# FYP_Programmer.net
KiCad netlist of a schematic drawn in EasyEDA
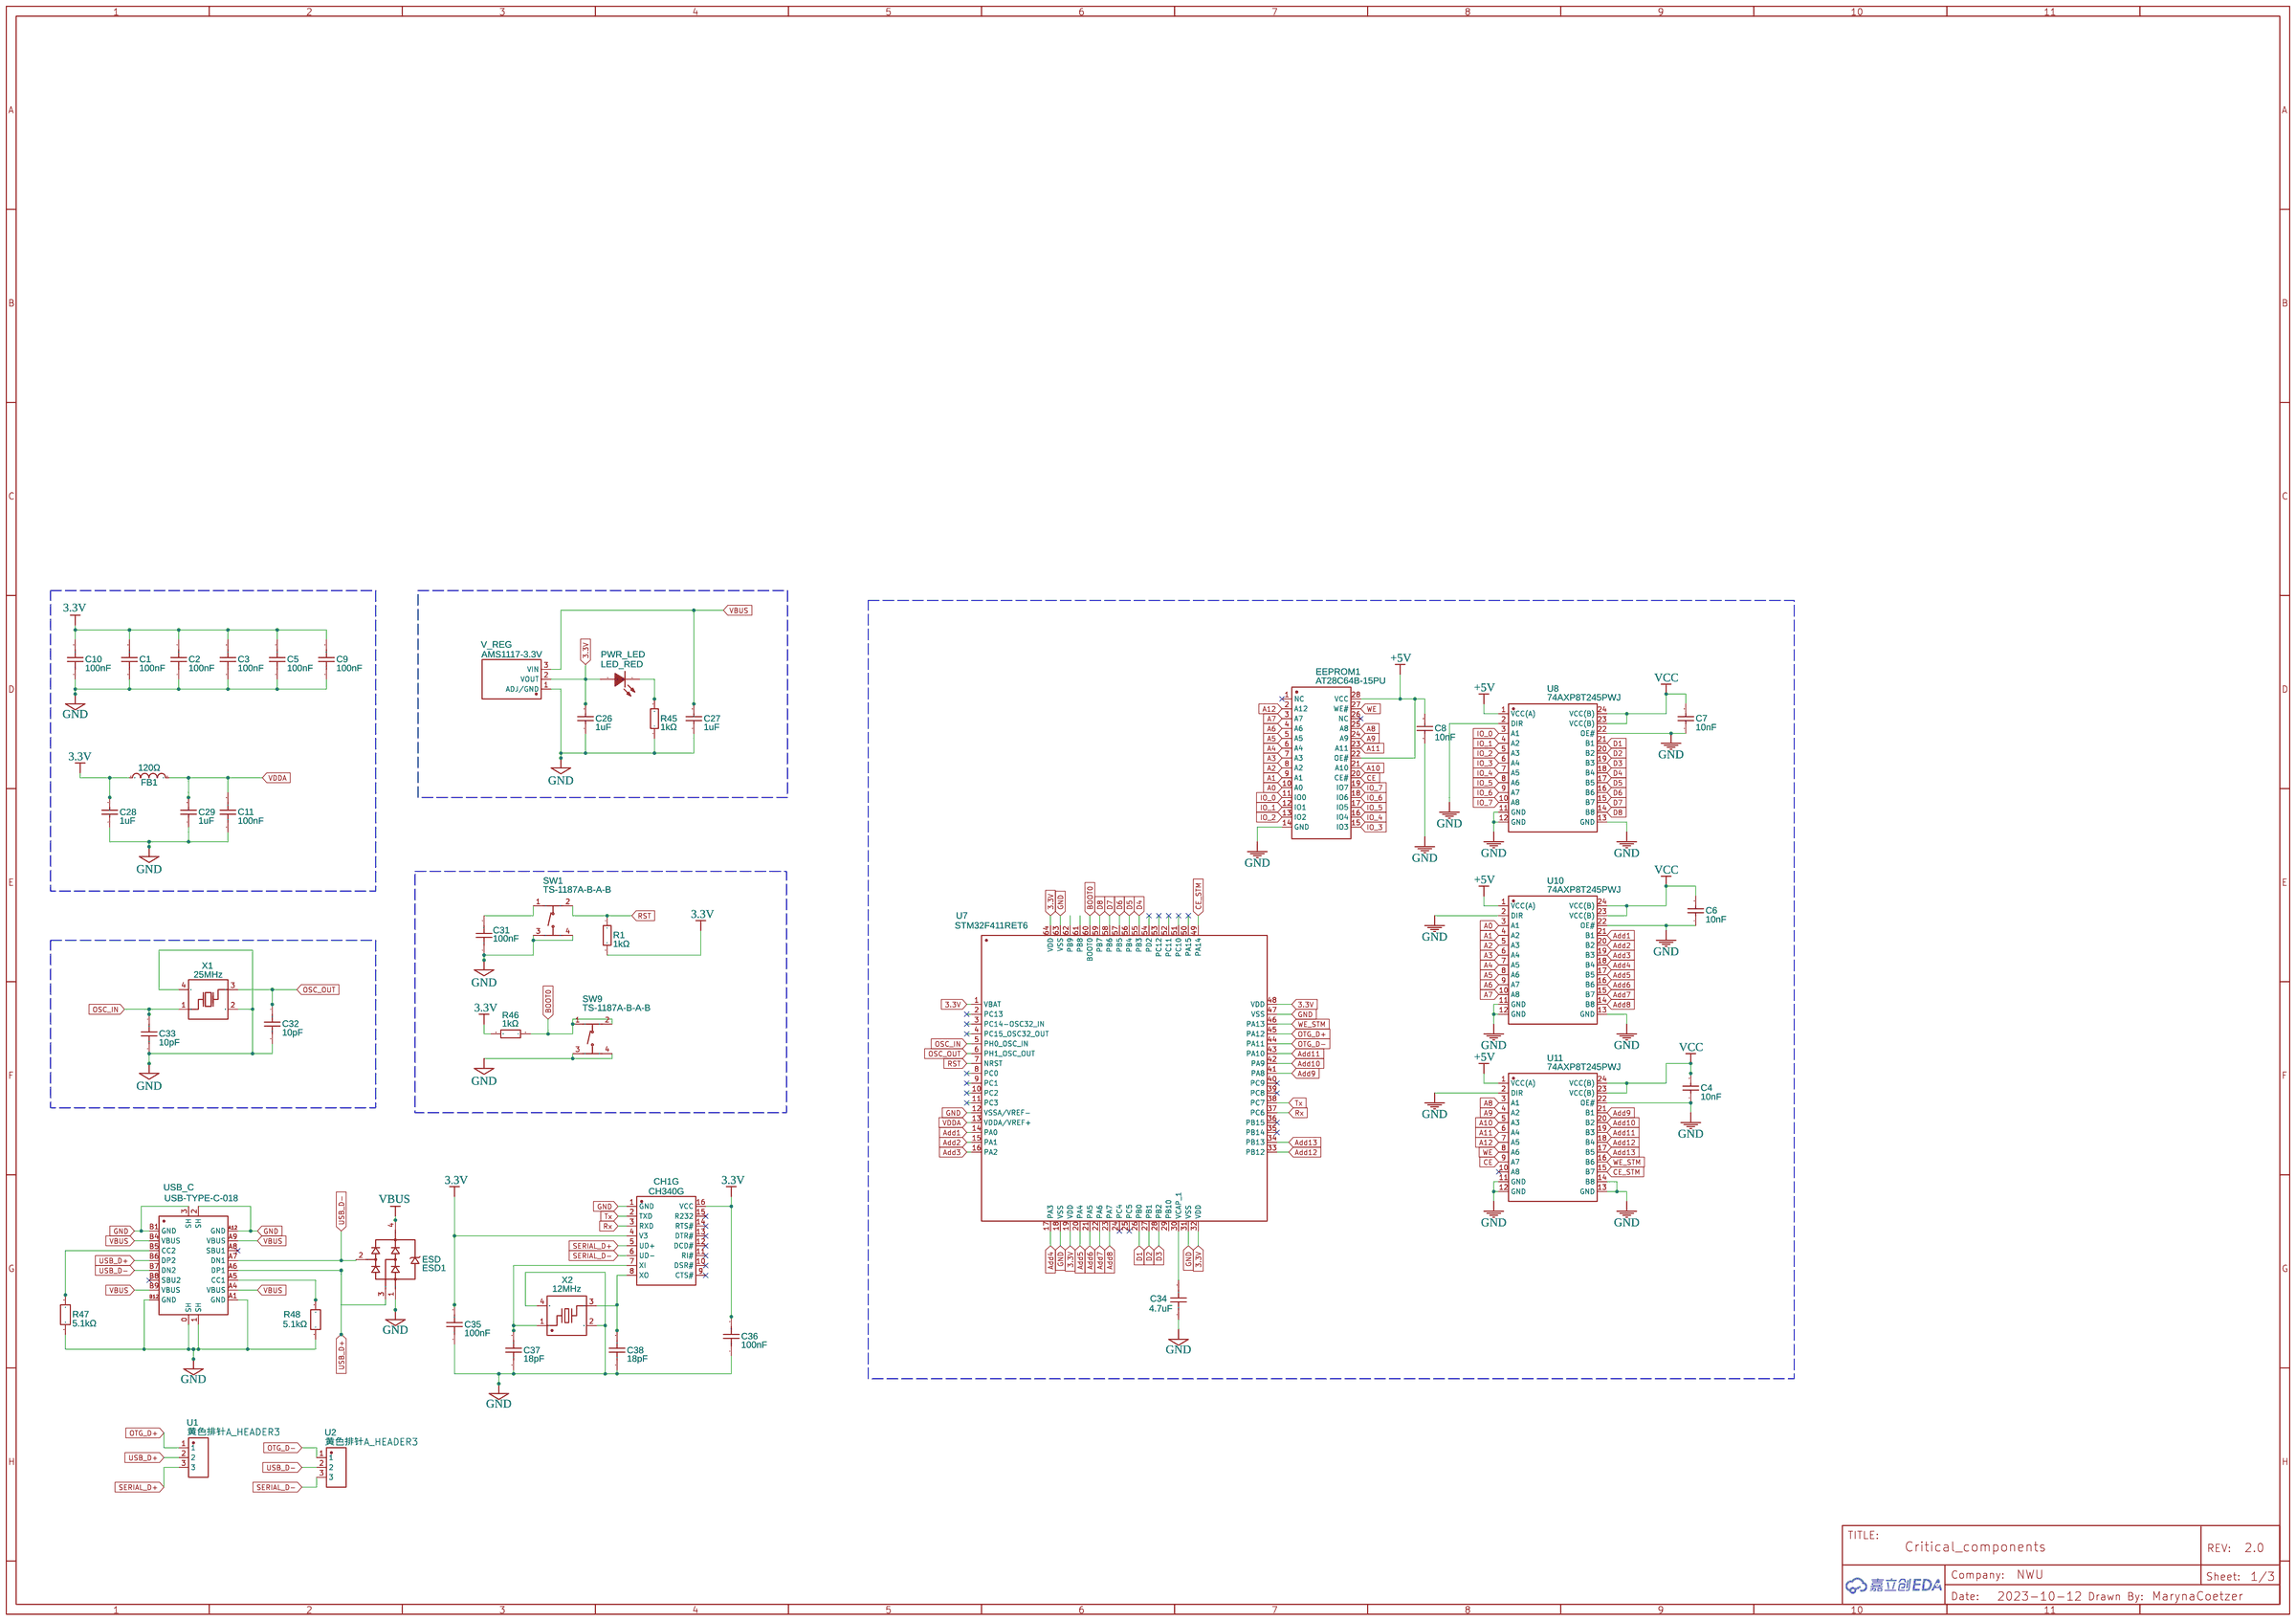
[diagram p0: schematic sheet]

(export (version "E")
  (design (tool "Eeschema 10.0.6"))
  (components
    (comp (ref "C1")
      (value "100nF")
      (fields
        (field (name "Manufacturer Part") "CC0603KRX7R9BB104")
        (field (name "Manufacturer") "YAGEO(国巨)")
      )
      (libsource (lib "") (part "CC0603KRX7R9BB104"))
    )
    (comp (ref "C2")
      (value "100nF")
      (fields
        (field (name "Manufacturer Part") "CC0603KRX7R9BB104")
        (field (name "Manufacturer") "YAGEO(国巨)")
      )
      (libsource (lib "") (part "CC0603KRX7R9BB104"))
    )
    (comp (ref "C3")
      (value "100nF")
      (fields
        (field (name "Manufacturer Part") "CC0603KRX7R9BB104")
        (field (name "Manufacturer") "YAGEO(国巨)")
      )
      (libsource (lib "") (part "CC0603KRX7R9BB104"))
    )
    (comp (ref "C4")
      (value "10nF")
      (fields (field (name "Manufacturer Part") "0603B103K500NT") (field (name "Manufacturer") "FH(风华)"))
      (libsource (lib "") (part "0603B103K500NT"))
    )
    (comp (ref "C5")
      (value "100nF")
      (fields
        (field (name "Manufacturer Part") "CC0603KRX7R9BB104")
        (field (name "Manufacturer") "YAGEO(国巨)")
      )
      (libsource (lib "") (part "CC0603KRX7R9BB104"))
    )
    (comp (ref "C6")
      (value "10nF")
      (fields (field (name "Manufacturer Part") "0603B103K500NT") (field (name "Manufacturer") "FH(风华)"))
      (libsource (lib "") (part "0603B103K500NT"))
    )
    (comp (ref "C7")
      (value "10nF")
      (fields (field (name "Manufacturer Part") "0603B103K500NT") (field (name "Manufacturer") "FH(风华)"))
      (libsource (lib "") (part "0603B103K500NT"))
    )
    (comp (ref "C8")
      (value "10nF")
      (fields (field (name "Manufacturer Part") "0603B103K500NT") (field (name "Manufacturer") "FH(风华)"))
      (libsource (lib "") (part "0603B103K500NT"))
    )
    (comp (ref "C9")
      (value "100nF")
      (fields
        (field (name "Manufacturer Part") "CC0603KRX7R9BB104")
        (field (name "Manufacturer") "YAGEO(国巨)")
      )
      (libsource (lib "") (part "CC0603KRX7R9BB104"))
    )
    (comp (ref "C10")
      (value "100nF")
      (fields
        (field (name "Manufacturer Part") "CC0603KRX7R9BB104")
        (field (name "Manufacturer") "YAGEO(国巨)")
      )
      (libsource (lib "") (part "CC0603KRX7R9BB104"))
    )
    (comp (ref "C11")
      (value "100nF")
      (fields
        (field (name "Manufacturer Part") "CC0603KRX7R9BB104")
        (field (name "Manufacturer") "YAGEO(国巨)")
      )
      (libsource (lib "") (part "CC0603KRX7R9BB104"))
    )
    (comp (ref "C26")
      (value "1uF")
      (fields (field (name "Manufacturer") "SAMSUNG(三星)"))
      (libsource (lib "") (part "CL10A105KB8NNNC"))
    )
    (comp (ref "C27")
      (value "1uF")
      (fields (field (name "Manufacturer") "SAMSUNG(三星)"))
      (libsource (lib "") (part "CL10A105KB8NNNC"))
    )
    (comp (ref "C28")
      (value "1uF")
      (fields (field (name "Manufacturer") "SAMSUNG(三星)"))
      (libsource (lib "") (part "CL10A105KB8NNNC"))
    )
    (comp (ref "C29")
      (value "1uF")
      (fields (field (name "Manufacturer") "SAMSUNG(三星)"))
      (libsource (lib "") (part "CL10A105KB8NNNC"))
    )
    (comp (ref "C31")
      (value "100nF")
      (fields (field (name "Manufacturer Part") "C1608X7R104KFTS") (field (name "Manufacturer") "DARFON(达方)"))
      (libsource (lib "") (part "C1608X7R104KFTS"))
    )
    (comp (ref "C32")
      (value "10pF")
      (fields (field (name "Manufacturer") "muRata(村田)"))
      (libsource (lib "") (part "GJM1555C1H100JB01D"))
    )
    (comp (ref "C33")
      (value "10pF")
      (fields (field (name "Manufacturer") "muRata(村田)"))
      (libsource (lib "") (part "GJM1555C1H100JB01D"))
    )
    (comp (ref "C34")
      (value "4.7uF")
      (fields (field (name "Manufacturer") "muRata(村田)"))
      (libsource (lib "") (part "GRM188R61C475KE11D"))
    )
    (comp (ref "C35")
      (value "100nF")
      (fields (field (name "Manufacturer") "Kyocera AVX"))
      (libsource (lib "") (part "06033C104K4T2A"))
    )
    (comp (ref "C36")
      (value "100nF")
      (fields (field (name "Manufacturer") "Kyocera AVX"))
      (libsource (lib "") (part "06033C104K4T2A"))
    )
    (comp (ref "C37")
      (value "18pF")
      (fields
        (field (name "Manufacturer Part") "AC0603JRNPO0BN220")
        (field (name "Manufacturer") "YAGEO(国巨)")
      )
      (libsource (lib "") (part "AC0603JRNPO0BN220"))
    )
    (comp (ref "C38")
      (value "18pF")
      (fields
        (field (name "Manufacturer Part") "AC0603JRNPO0BN220")
        (field (name "Manufacturer") "YAGEO(国巨)")
      )
      (libsource (lib "") (part "AC0603JRNPO0BN220"))
    )
    (comp (ref "CH1G")
      (value "CH340G")
      (fields (field (name "Manufacturer") "WCH(南京沁恒)"))
      (libsource (lib "") (part "CH340G"))
    )
    (comp (ref "EEPROM1")
      (value "AT28C64B-15PU")
      (fields (field (name "Manufacturer") "MICROCHIP(美国微芯)"))
      (libsource (lib "") (part "AT28C64B-15PU"))
    )
    (comp (ref "ESD")
      (value "ESD1")
      (fields
        (field (name "Manufacturer Part") "TPPRTR5V0U2X")
        (field (name "Manufacturer") "TECH PUBLIC(台舟)")
      )
      (libsource (lib "") (part "TPPRTR5V0U2X"))
    )
    (comp (ref "FB1")
      (value "120Ω")
      (fields (field (name "Manufacturer Part") "GZ1608D121TF") (field (name "Manufacturer") "Sunlord(顺络)"))
      (libsource (lib "") (part "GZ1608D121TF-C12391"))
    )
    (comp (ref "PWR_LED")
      (value "LED_RED")
      (fields (field (name "Manufacturer") "国星光电"))
      (libsource (lib "") (part "FC-2012HRK-620D"))
    )
    (comp (ref "R1")
      (value "1kΩ")
      (fields (field (name "Manufacturer") "UNI-ROYAL(厚声)"))
      (libsource (lib "") (part "0603WAF1001T5E_1"))
    )
    (comp (ref "R45")
      (value "1kΩ")
      (fields (field (name "Manufacturer Part") "RMS06FT1001") (field (name "Manufacturer") "大毅科技"))
      (libsource (lib "") (part "RMS06FT1001"))
    )
    (comp (ref "R46")
      (value "1kΩ")
      (fields (field (name "Manufacturer") "UNI-ROYAL(厚声)"))
      (libsource (lib "") (part "0603WAF1001T5E"))
    )
    (comp (ref "R47")
      (value "5.1kΩ")
      (fields
        (field (name "Manufacturer Part") "CQ03WAJ0512T5E")
        (field (name "Manufacturer") "UNI-ROYAL(厚声)")
      )
      (libsource (lib "") (part "CQ03WAJ0512T5E"))
    )
    (comp (ref "R48")
      (value "5.1kΩ")
      (fields
        (field (name "Manufacturer Part") "CQ03WAJ0512T5E")
        (field (name "Manufacturer") "UNI-ROYAL(厚声)")
      )
      (libsource (lib "") (part "CQ03WAJ0512T5E"))
    )
    (comp (ref "SW1")
      (value "TS-1187A-B-A-B")
      (fields (field (name "Manufacturer") "XKB Connection(中国星坤)"))
      (libsource (lib "") (part "TS-1187A-B-A-B"))
    )
    (comp (ref "SW9")
      (value "TS-1187A-B-A-B")
      (fields (field (name "Manufacturer") "XKB Connection(中国星坤)"))
      (libsource (lib "") (part "TS-1187A-B-A-B"))
    )
    (comp (ref "U1") (value "黄色排针A_HEADER3") (libsource (lib "") (part "黄色排针A_HEADER3")))
    (comp (ref "U2") (value "黄色排针A_HEADER3") (libsource (lib "") (part "黄色排针A_HEADER3")))
    (comp (ref "U7")
      (value "STM32F411RET6")
      (fields (field (name "Manufacturer") "ST(意法半导体)"))
      (libsource (lib "") (part "STM32F411RET6"))
    )
    (comp (ref "U8")
      (value "74AXP8T245PWJ")
      (fields (field (name "Manufacturer") "Nexperia(安世)"))
      (libsource (lib "") (part "74AXP8T245PWJ"))
    )
    (comp (ref "U10")
      (value "74AXP8T245PWJ")
      (fields (field (name "Manufacturer") "Nexperia(安世)"))
      (libsource (lib "") (part "74AXP8T245PWJ"))
    )
    (comp (ref "U11")
      (value "74AXP8T245PWJ")
      (fields (field (name "Manufacturer") "Nexperia(安世)"))
      (libsource (lib "") (part "74AXP8T245PWJ"))
    )
    (comp (ref "USB_C")
      (value "USB-TYPE-C-018")
      (fields (field (name "Manufacturer") "DEALON(德艺隆)"))
      (libsource (lib "") (part "USB-TYPE-C-018"))
    )
    (comp (ref "V_REG")
      (value "AMS1117-3.3V")
      (fields (field (name "Manufacturer") "MSKSEMI(美森科)"))
      (libsource (lib "") (part "AMS1117-3.3V_C5120796"))
    )
    (comp (ref "X1")
      (value "25MHz")
      (fields (field (name "Manufacturer Part") "X322525MMB4SI") (field (name "Manufacturer") "YXC(扬兴晶振)"))
      (libsource (lib "") (part "X322525MMB4SI"))
    )
    (comp (ref "X2")
      (value "12MHz")
      (fields (field (name "Manufacturer") "HD(浩都频率)"))
      (libsource (lib "") (part "7B012000Q01"))
    )
  )
  (nets
    (net (code "1") (name "+5V") (class "Default")
      (node (ref "C8") (pin "2") (pinfunction "2_2") (pintype "input"))
      (node (ref "EEPROM1") (pin "22") (pinfunction "OE#_22") (pintype "unspecified"))
      (node (ref "EEPROM1") (pin "28") (pinfunction "VCC_28") (pintype "unspecified"))
      (node (ref "U10") (pin "1") (pinfunction "VCC(A)_1") (pintype "unspecified"))
      (node (ref "U11") (pin "1") (pinfunction "VCC(A)_1") (pintype "unspecified"))
      (node (ref "U8") (pin "1") (pinfunction "VCC(A)_1") (pintype "unspecified"))
    )
    (net (code "2") (name "3.3V") (class "Default")
      (node (ref "C1") (pin "2") (pinfunction "2_2") (pintype "unspecified"))
      (node (ref "C10") (pin "2") (pinfunction "2_2") (pintype "unspecified"))
      (node (ref "C2") (pin "2") (pinfunction "2_2") (pintype "unspecified"))
      (node (ref "C26") (pin "2") (pinfunction "2_2") (pintype "input"))
      (node (ref "C28") (pin "2") (pinfunction "2_2") (pintype "input"))
      (node (ref "C3") (pin "2") (pinfunction "2_2") (pintype "unspecified"))
      (node (ref "C35") (pin "2") (pinfunction "2_2") (pintype "unspecified"))
      (node (ref "C36") (pin "2") (pinfunction "2_2") (pintype "unspecified"))
      (node (ref "C5") (pin "2") (pinfunction "2_2") (pintype "unspecified"))
      (node (ref "C9") (pin "2") (pinfunction "2_2") (pintype "unspecified"))
      (node (ref "CH1G") (pin "16") (pinfunction "VCC_16") (pintype "unspecified"))
      (node (ref "CH1G") (pin "4") (pinfunction "V3_4") (pintype "unspecified"))
      (node (ref "FB1") (pin "1") (pinfunction "1_1") (pintype "unspecified"))
      (node (ref "PWR_LED") (pin "2") (pinfunction "+_2") (pintype "unspecified"))
      (node (ref "R1") (pin "2") (pinfunction "2_2") (pintype "input"))
      (node (ref "R46") (pin "2") (pinfunction "2_2") (pintype "input"))
      (node (ref "U7") (pin "1") (pinfunction "VBAT_1") (pintype "unspecified"))
      (node (ref "U7") (pin "19") (pinfunction "VDD_19") (pintype "unspecified"))
      (node (ref "U7") (pin "32") (pinfunction "VDD_32") (pintype "unspecified"))
      (node (ref "U7") (pin "48") (pinfunction "VDD_48") (pintype "unspecified"))
      (node (ref "U7") (pin "64") (pinfunction "VDD_64") (pintype "unspecified"))
      (node (ref "V_REG") (pin "2") (pinfunction "VOUT_2") (pintype "unspecified"))
    )
    (net (code "3") (name "A0") (class "Default")
      (node (ref "EEPROM1") (pin "10") (pinfunction "A0_10") (pintype "unspecified"))
      (node (ref "U10") (pin "3") (pinfunction "A1_3") (pintype "unspecified"))
    )
    (net (code "4") (name "A1") (class "Default")
      (node (ref "EEPROM1") (pin "9") (pinfunction "A1_9") (pintype "unspecified"))
      (node (ref "U10") (pin "4") (pinfunction "A2_4") (pintype "unspecified"))
    )
    (net (code "5") (name "A2") (class "Default")
      (node (ref "EEPROM1") (pin "8") (pinfunction "A2_8") (pintype "unspecified"))
      (node (ref "U10") (pin "5") (pinfunction "A3_5") (pintype "unspecified"))
    )
    (net (code "6") (name "A3") (class "Default")
      (node (ref "EEPROM1") (pin "7") (pinfunction "A3_7") (pintype "unspecified"))
      (node (ref "U10") (pin "6") (pinfunction "A4_6") (pintype "unspecified"))
    )
    (net (code "7") (name "A4") (class "Default")
      (node (ref "EEPROM1") (pin "6") (pinfunction "A4_6") (pintype "unspecified"))
      (node (ref "U10") (pin "7") (pinfunction "A5_7") (pintype "unspecified"))
    )
    (net (code "8") (name "A5") (class "Default")
      (node (ref "EEPROM1") (pin "5") (pinfunction "A5_5") (pintype "unspecified"))
      (node (ref "U10") (pin "8") (pinfunction "A6_8") (pintype "unspecified"))
    )
    (net (code "9") (name "A6") (class "Default")
      (node (ref "EEPROM1") (pin "4") (pinfunction "A6_4") (pintype "unspecified"))
      (node (ref "U10") (pin "9") (pinfunction "A7_9") (pintype "unspecified"))
    )
    (net (code "10") (name "A7") (class "Default")
      (node (ref "EEPROM1") (pin "3") (pinfunction "A7_3") (pintype "unspecified"))
      (node (ref "U10") (pin "10") (pinfunction "A8_10") (pintype "unspecified"))
    )
    (net (code "11") (name "A8") (class "Default")
      (node (ref "EEPROM1") (pin "25") (pinfunction "A8_25") (pintype "unspecified"))
      (node (ref "U11") (pin "3") (pinfunction "A1_3") (pintype "unspecified"))
    )
    (net (code "12") (name "A9") (class "Default")
      (node (ref "EEPROM1") (pin "24") (pinfunction "A9_24") (pintype "unspecified"))
      (node (ref "U11") (pin "4") (pinfunction "A2_4") (pintype "unspecified"))
    )
    (net (code "13") (name "A10") (class "Default")
      (node (ref "EEPROM1") (pin "21") (pinfunction "A10_21") (pintype "unspecified"))
      (node (ref "U11") (pin "5") (pinfunction "A3_5") (pintype "unspecified"))
    )
    (net (code "14") (name "A11") (class "Default")
      (node (ref "EEPROM1") (pin "23") (pinfunction "A11_23") (pintype "unspecified"))
      (node (ref "U11") (pin "6") (pinfunction "A4_6") (pintype "unspecified"))
    )
    (net (code "15") (name "A12") (class "Default")
      (node (ref "EEPROM1") (pin "2") (pinfunction "A12_2") (pintype "unspecified"))
      (node (ref "U11") (pin "7") (pinfunction "A5_7") (pintype "unspecified"))
    )
    (net (code "16") (name "Add1") (class "Default")
      (node (ref "U10") (pin "21") (pinfunction "B1_21") (pintype "unspecified"))
      (node (ref "U7") (pin "14") (pinfunction "PA0_14") (pintype "unspecified"))
    )
    (net (code "17") (name "Add2") (class "Default")
      (node (ref "U10") (pin "20") (pinfunction "B2_20") (pintype "unspecified"))
      (node (ref "U7") (pin "15") (pinfunction "PA1_15") (pintype "unspecified"))
    )
    (net (code "18") (name "Add3") (class "Default")
      (node (ref "U10") (pin "19") (pinfunction "B3_19") (pintype "unspecified"))
      (node (ref "U7") (pin "16") (pinfunction "PA2_16") (pintype "unspecified"))
    )
    (net (code "19") (name "Add4") (class "Default")
      (node (ref "U10") (pin "18") (pinfunction "B4_18") (pintype "unspecified"))
      (node (ref "U7") (pin "17") (pinfunction "PA3_17") (pintype "unspecified"))
    )
    (net (code "20") (name "Add5") (class "Default")
      (node (ref "U10") (pin "17") (pinfunction "B5_17") (pintype "unspecified"))
      (node (ref "U7") (pin "20") (pinfunction "PA4_20") (pintype "unspecified"))
    )
    (net (code "21") (name "Add6") (class "Default")
      (node (ref "U10") (pin "16") (pinfunction "B6_16") (pintype "unspecified"))
      (node (ref "U7") (pin "21") (pinfunction "PA5_21") (pintype "unspecified"))
    )
    (net (code "22") (name "Add7") (class "Default")
      (node (ref "U10") (pin "15") (pinfunction "B7_15") (pintype "unspecified"))
      (node (ref "U7") (pin "22") (pinfunction "PA6_22") (pintype "unspecified"))
    )
    (net (code "23") (name "Add8") (class "Default")
      (node (ref "U10") (pin "14") (pinfunction "B8_14") (pintype "unspecified"))
      (node (ref "U7") (pin "23") (pinfunction "PA7_23") (pintype "unspecified"))
    )
    (net (code "24") (name "Add9") (class "Default")
      (node (ref "U11") (pin "21") (pinfunction "B1_21") (pintype "unspecified"))
      (node (ref "U7") (pin "41") (pinfunction "PA8_41") (pintype "unspecified"))
    )
    (net (code "25") (name "Add10") (class "Default")
      (node (ref "U11") (pin "20") (pinfunction "B2_20") (pintype "unspecified"))
      (node (ref "U7") (pin "42") (pinfunction "PA9_42") (pintype "unspecified"))
    )
    (net (code "26") (name "Add11") (class "Default")
      (node (ref "U11") (pin "19") (pinfunction "B3_19") (pintype "unspecified"))
      (node (ref "U7") (pin "43") (pinfunction "PA10_43") (pintype "unspecified"))
    )
    (net (code "27") (name "Add12") (class "Default")
      (node (ref "U11") (pin "18") (pinfunction "B4_18") (pintype "unspecified"))
      (node (ref "U7") (pin "33") (pinfunction "PB12_33") (pintype "unspecified"))
    )
    (net (code "28") (name "Add13") (class "Default")
      (node (ref "U11") (pin "17") (pinfunction "B5_17") (pintype "unspecified"))
      (node (ref "U7") (pin "34") (pinfunction "PB13_34") (pintype "unspecified"))
    )
    (net (code "29") (name "BOOT0") (class "Default")
      (node (ref "R46") (pin "1") (pinfunction "1_1") (pintype "input"))
      (node (ref "SW9") (pin "1") (pinfunction "A_1") (pintype "unspecified"))
      (node (ref "SW9") (pin "2") (pinfunction "B_2") (pintype "unspecified"))
      (node (ref "U7") (pin "60") (pinfunction "BOOT0_60") (pintype "unspecified"))
    )
    (net (code "30") (name "CE") (class "Default")
      (node (ref "EEPROM1") (pin "20") (pinfunction "CE#_20") (pintype "unspecified"))
      (node (ref "U11") (pin "9") (pinfunction "A7_9") (pintype "unspecified"))
    )
    (net (code "31") (name "CE_STM") (class "Default")
      (node (ref "U11") (pin "15") (pinfunction "B7_15") (pintype "unspecified"))
      (node (ref "U7") (pin "49") (pinfunction "PA14_49") (pintype "unspecified"))
    )
    (net (code "32") (name "D1") (class "Default")
      (node (ref "U7") (pin "26") (pinfunction "PB0_26") (pintype "unspecified"))
      (node (ref "U8") (pin "21") (pinfunction "B1_21") (pintype "unspecified"))
    )
    (net (code "33") (name "D2") (class "Default")
      (node (ref "U7") (pin "27") (pinfunction "PB1_27") (pintype "unspecified"))
      (node (ref "U8") (pin "20") (pinfunction "B2_20") (pintype "unspecified"))
    )
    (net (code "34") (name "D3") (class "Default")
      (node (ref "U7") (pin "28") (pinfunction "PB2_28") (pintype "unspecified"))
      (node (ref "U8") (pin "19") (pinfunction "B3_19") (pintype "unspecified"))
    )
    (net (code "35") (name "D4") (class "Default")
      (node (ref "U7") (pin "55") (pinfunction "PB3_55") (pintype "unspecified"))
      (node (ref "U8") (pin "18") (pinfunction "B4_18") (pintype "unspecified"))
    )
    (net (code "36") (name "D5") (class "Default")
      (node (ref "U7") (pin "56") (pinfunction "PB4_56") (pintype "unspecified"))
      (node (ref "U8") (pin "17") (pinfunction "B5_17") (pintype "unspecified"))
    )
    (net (code "37") (name "D6") (class "Default")
      (node (ref "U7") (pin "57") (pinfunction "PB5_57") (pintype "unspecified"))
      (node (ref "U8") (pin "16") (pinfunction "B6_16") (pintype "unspecified"))
    )
    (net (code "38") (name "D7") (class "Default")
      (node (ref "U7") (pin "58") (pinfunction "PB6_58") (pintype "unspecified"))
      (node (ref "U8") (pin "15") (pinfunction "B7_15") (pintype "unspecified"))
    )
    (net (code "39") (name "D8") (class "Default")
      (node (ref "U7") (pin "59") (pinfunction "PB7_59") (pintype "unspecified"))
      (node (ref "U8") (pin "14") (pinfunction "B8_14") (pintype "unspecified"))
    )
    (net (code "40") (name "GND") (class "Default")
      (node (ref "C1") (pin "1") (pinfunction "1_1") (pintype "unspecified"))
      (node (ref "C10") (pin "1") (pinfunction "1_1") (pintype "unspecified"))
      (node (ref "C11") (pin "1") (pinfunction "1_1") (pintype "unspecified"))
      (node (ref "C2") (pin "1") (pinfunction "1_1") (pintype "unspecified"))
      (node (ref "C26") (pin "1") (pinfunction "1_1") (pintype "input"))
      (node (ref "C27") (pin "1") (pinfunction "1_1") (pintype "input"))
      (node (ref "C28") (pin "1") (pinfunction "1_1") (pintype "input"))
      (node (ref "C29") (pin "1") (pinfunction "1_1") (pintype "input"))
      (node (ref "C3") (pin "1") (pinfunction "1_1") (pintype "unspecified"))
      (node (ref "C31") (pin "1") (pinfunction "1_1") (pintype "unspecified"))
      (node (ref "C32") (pin "2") (pinfunction "2_2") (pintype "unspecified"))
      (node (ref "C33") (pin "2") (pinfunction "2_2") (pintype "unspecified"))
      (node (ref "C34") (pin "1") (pinfunction "1_1") (pintype "unspecified"))
      (node (ref "C35") (pin "1") (pinfunction "1_1") (pintype "unspecified"))
      (node (ref "C36") (pin "1") (pinfunction "1_1") (pintype "unspecified"))
      (node (ref "C37") (pin "1") (pinfunction "1_1") (pintype "unspecified"))
      (node (ref "C38") (pin "1") (pinfunction "1_1") (pintype "unspecified"))
      (node (ref "C4") (pin "1") (pinfunction "1_1") (pintype "input"))
      (node (ref "C5") (pin "1") (pinfunction "1_1") (pintype "unspecified"))
      (node (ref "C6") (pin "1") (pinfunction "1_1") (pintype "input"))
      (node (ref "C7") (pin "1") (pinfunction "1_1") (pintype "input"))
      (node (ref "C8") (pin "1") (pinfunction "1_1") (pintype "input"))
      (node (ref "C9") (pin "1") (pinfunction "1_1") (pintype "unspecified"))
      (node (ref "CH1G") (pin "1") (pinfunction "GND_1") (pintype "unspecified"))
      (node (ref "EEPROM1") (pin "14") (pinfunction "GND_14") (pintype "unspecified"))
      (node (ref "ESD") (pin "1") (pinfunction "1_1") (pintype "unspecified"))
      (node (ref "R45") (pin "1") (pinfunction "1_1") (pintype "unspecified"))
      (node (ref "R47") (pin "1") (pinfunction "1_1") (pintype "unspecified"))
      (node (ref "R48") (pin "1") (pinfunction "1_1") (pintype "unspecified"))
      (node (ref "SW1") (pin "3") (pinfunction "C_3") (pintype "unspecified"))
      (node (ref "SW1") (pin "4") (pinfunction "D_4") (pintype "unspecified"))
      (node (ref "SW9") (pin "3") (pinfunction "C_3") (pintype "unspecified"))
      (node (ref "SW9") (pin "4") (pinfunction "D_4") (pintype "unspecified"))
      (node (ref "U10") (pin "11") (pinfunction "GND_11") (pintype "unspecified"))
      (node (ref "U10") (pin "12") (pinfunction "GND_12") (pintype "unspecified"))
      (node (ref "U10") (pin "13") (pinfunction "GND_13") (pintype "unspecified"))
      (node (ref "U10") (pin "2") (pinfunction "DIR_2") (pintype "unspecified"))
      (node (ref "U10") (pin "22") (pinfunction "OE#_22") (pintype "unspecified"))
      (node (ref "U11") (pin "11") (pinfunction "GND_11") (pintype "unspecified"))
      (node (ref "U11") (pin "12") (pinfunction "GND_12") (pintype "unspecified"))
      (node (ref "U11") (pin "13") (pinfunction "GND_13") (pintype "unspecified"))
      (node (ref "U11") (pin "14") (pinfunction "B8_14") (pintype "unspecified"))
      (node (ref "U11") (pin "2") (pinfunction "DIR_2") (pintype "unspecified"))
      (node (ref "U11") (pin "22") (pinfunction "OE#_22") (pintype "unspecified"))
      (node (ref "U7") (pin "12") (pinfunction "VSSA/VREF-_12") (pintype "unspecified"))
      (node (ref "U7") (pin "18") (pinfunction "VSS_18") (pintype "unspecified"))
      (node (ref "U7") (pin "31") (pinfunction "VSS_31") (pintype "unspecified"))
      (node (ref "U7") (pin "47") (pinfunction "VSS_47") (pintype "unspecified"))
      (node (ref "U7") (pin "63") (pinfunction "VSS_63") (pintype "unspecified"))
      (node (ref "U8") (pin "11") (pinfunction "GND_11") (pintype "unspecified"))
      (node (ref "U8") (pin "12") (pinfunction "GND_12") (pintype "unspecified"))
      (node (ref "U8") (pin "13") (pinfunction "GND_13") (pintype "unspecified"))
      (node (ref "U8") (pin "2") (pinfunction "DIR_2") (pintype "unspecified"))
      (node (ref "U8") (pin "22") (pinfunction "OE#_22") (pintype "unspecified"))
      (node (ref "USB_C") (pin "0") (pinfunction "SH_0") (pintype "unspecified"))
      (node (ref "USB_C") (pin "1") (pinfunction "SH_1") (pintype "unspecified"))
      (node (ref "USB_C") (pin "2") (pinfunction "SH_2") (pintype "unspecified"))
      (node (ref "USB_C") (pin "3") (pinfunction "SH_3") (pintype "unspecified"))
      (node (ref "USB_C") (pin "A1") (pinfunction "GND_A1") (pintype "unspecified"))
      (node (ref "USB_C") (pin "A12") (pinfunction "GND_A12") (pintype "unspecified"))
      (node (ref "USB_C") (pin "B1") (pinfunction "GND_B1") (pintype "unspecified"))
      (node (ref "USB_C") (pin "B12") (pinfunction "GND_B12") (pintype "unspecified"))
      (node (ref "V_REG") (pin "1") (pinfunction "ADJ/GND_1") (pintype "unspecified"))
      (node (ref "X1") (pin "2") (pinfunction "GND_2") (pintype "unspecified"))
      (node (ref "X1") (pin "4") (pinfunction "GND_4") (pintype "unspecified"))
      (node (ref "X2") (pin "2") (pinfunction "GND_2") (pintype "input"))
      (node (ref "X2") (pin "4") (pinfunction "GND_4") (pintype "input"))
    )
    (net (code "41") (name "IO_0") (class "Default")
      (node (ref "EEPROM1") (pin "11") (pinfunction "IO0_11") (pintype "unspecified"))
      (node (ref "U8") (pin "3") (pinfunction "A1_3") (pintype "unspecified"))
    )
    (net (code "42") (name "IO_1") (class "Default")
      (node (ref "EEPROM1") (pin "12") (pinfunction "IO1_12") (pintype "unspecified"))
      (node (ref "U8") (pin "4") (pinfunction "A2_4") (pintype "unspecified"))
    )
    (net (code "43") (name "IO_2") (class "Default")
      (node (ref "EEPROM1") (pin "13") (pinfunction "IO2_13") (pintype "unspecified"))
      (node (ref "U8") (pin "5") (pinfunction "A3_5") (pintype "unspecified"))
    )
    (net (code "44") (name "IO_3") (class "Default")
      (node (ref "EEPROM1") (pin "15") (pinfunction "IO3_15") (pintype "unspecified"))
      (node (ref "U8") (pin "6") (pinfunction "A4_6") (pintype "unspecified"))
    )
    (net (code "45") (name "IO_4") (class "Default")
      (node (ref "EEPROM1") (pin "16") (pinfunction "IO4_16") (pintype "unspecified"))
      (node (ref "U8") (pin "7") (pinfunction "A5_7") (pintype "unspecified"))
    )
    (net (code "46") (name "IO_5") (class "Default")
      (node (ref "EEPROM1") (pin "17") (pinfunction "IO5_17") (pintype "unspecified"))
      (node (ref "U8") (pin "8") (pinfunction "A6_8") (pintype "unspecified"))
    )
    (net (code "47") (name "IO_6") (class "Default")
      (node (ref "EEPROM1") (pin "18") (pinfunction "IO6_18") (pintype "unspecified"))
      (node (ref "U8") (pin "9") (pinfunction "A7_9") (pintype "unspecified"))
    )
    (net (code "48") (name "IO_7") (class "Default")
      (node (ref "EEPROM1") (pin "19") (pinfunction "IO7_19") (pintype "unspecified"))
      (node (ref "U8") (pin "10") (pinfunction "A8_10") (pintype "unspecified"))
    )
    (net (code "49") (name "Net-(CH1G-XI)") (class "Default")
      (node (ref "C37") (pin "2") (pinfunction "2_2") (pintype "unspecified"))
      (node (ref "CH1G") (pin "7") (pinfunction "XI_7") (pintype "unspecified"))
      (node (ref "X2") (pin "1") (pinfunction "1_1") (pintype "input"))
    )
    (net (code "50") (name "Net-(CH1G-XO)") (class "Default")
      (node (ref "C38") (pin "2") (pinfunction "2_2") (pintype "unspecified"))
      (node (ref "CH1G") (pin "8") (pinfunction "XO_8") (pintype "unspecified"))
      (node (ref "X2") (pin "3") (pinfunction "3_3") (pintype "input"))
    )
    (net (code "51") (name "Net-(PWR_LED--)") (class "Default")
      (node (ref "PWR_LED") (pin "1") (pinfunction "-_1") (pintype "unspecified"))
      (node (ref "R45") (pin "2") (pinfunction "2_2") (pintype "unspecified"))
    )
    (net (code "52") (name "Net-(SW1-A)") (class "Default")
      (node (ref "C31") (pin "2") (pinfunction "2_2") (pintype "unspecified"))
      (node (ref "SW1") (pin "1") (pinfunction "A_1") (pintype "unspecified"))
    )
    (net (code "53") (name "Net-(U7-VCAP_1)") (class "Default")
      (node (ref "C34") (pin "2") (pinfunction "2_2") (pintype "unspecified"))
      (node (ref "U7") (pin "30") (pinfunction "VCAP_1_30") (pintype "unspecified"))
    )
    (net (code "54") (name "Net-(USB_C-CC1)") (class "Default")
      (node (ref "R48") (pin "2") (pinfunction "2_2") (pintype "unspecified"))
      (node (ref "USB_C") (pin "A5") (pinfunction "CC1_A5") (pintype "unspecified"))
    )
    (net (code "55") (name "Net-(USB_C-CC2)") (class "Default")
      (node (ref "R47") (pin "2") (pinfunction "2_2") (pintype "unspecified"))
      (node (ref "USB_C") (pin "B5") (pinfunction "CC2_B5") (pintype "unspecified"))
    )
    (net (code "56") (name "OSC_IN") (class "Default")
      (node (ref "C33") (pin "1") (pinfunction "1_1") (pintype "unspecified"))
      (node (ref "U7") (pin "5") (pinfunction "PH0_OSC_IN_5") (pintype "unspecified"))
      (node (ref "X1") (pin "1") (pinfunction "OSC1_1") (pintype "unspecified"))
    )
    (net (code "57") (name "OSC_OUT") (class "Default")
      (node (ref "C32") (pin "1") (pinfunction "1_1") (pintype "unspecified"))
      (node (ref "U7") (pin "6") (pinfunction "PH1_OSC_OUT_6") (pintype "unspecified"))
      (node (ref "X1") (pin "3") (pinfunction "OSC2_3") (pintype "unspecified"))
    )
    (net (code "58") (name "OTG_D+") (class "Default")
      (node (ref "U1") (pin "1") (pinfunction "1_1") (pintype "unspecified"))
      (node (ref "U7") (pin "45") (pinfunction "PA12_45") (pintype "unspecified"))
    )
    (net (code "59") (name "OTG_D-") (class "Default")
      (node (ref "U2") (pin "1") (pinfunction "1_1") (pintype "unspecified"))
      (node (ref "U7") (pin "44") (pinfunction "PA11_44") (pintype "unspecified"))
    )
    (net (code "60") (name "RST") (class "Default")
      (node (ref "R1") (pin "1") (pinfunction "1_1") (pintype "input"))
      (node (ref "SW1") (pin "2") (pinfunction "B_2") (pintype "unspecified"))
      (node (ref "U7") (pin "7") (pinfunction "NRST_7") (pintype "unspecified"))
    )
    (net (code "61") (name "Rx") (class "Default")
      (node (ref "CH1G") (pin "3") (pinfunction "RXD_3") (pintype "unspecified"))
      (node (ref "U7") (pin "37") (pinfunction "PC6_37") (pintype "unspecified"))
    )
    (net (code "62") (name "SERIAL_D+") (class "Default")
      (node (ref "CH1G") (pin "5") (pinfunction "UD+_5") (pintype "unspecified"))
      (node (ref "U1") (pin "3") (pinfunction "3_3") (pintype "unspecified"))
    )
    (net (code "63") (name "SERIAL_D-") (class "Default")
      (node (ref "CH1G") (pin "6") (pinfunction "UD-_6") (pintype "unspecified"))
      (node (ref "U2") (pin "3") (pinfunction "3_3") (pintype "unspecified"))
    )
    (net (code "64") (name "Tx") (class "Default")
      (node (ref "CH1G") (pin "2") (pinfunction "TXD_2") (pintype "unspecified"))
      (node (ref "U7") (pin "38") (pinfunction "PC7_38") (pintype "unspecified"))
    )
    (net (code "65") (name "USB_D+") (class "Default")
      (node (ref "ESD") (pin "3") (pinfunction "3_3") (pintype "unspecified"))
      (node (ref "U1") (pin "2") (pinfunction "2_2") (pintype "unspecified"))
      (node (ref "USB_C") (pin "A6") (pinfunction "DP1_A6") (pintype "unspecified"))
      (node (ref "USB_C") (pin "B6") (pinfunction "DP2_B6") (pintype "unspecified"))
    )
    (net (code "66") (name "USB_D-") (class "Default")
      (node (ref "ESD") (pin "2") (pinfunction "2_2") (pintype "unspecified"))
      (node (ref "U2") (pin "2") (pinfunction "2_2") (pintype "unspecified"))
      (node (ref "USB_C") (pin "A7") (pinfunction "DN1_A7") (pintype "unspecified"))
      (node (ref "USB_C") (pin "B7") (pinfunction "DN2_B7") (pintype "unspecified"))
    )
    (net (code "67") (name "VBUS") (class "Default")
      (node (ref "C27") (pin "2") (pinfunction "2_2") (pintype "input"))
      (node (ref "ESD") (pin "4") (pinfunction "4_4") (pintype "unspecified"))
      (node (ref "USB_C") (pin "A4") (pinfunction "VBUS_A4") (pintype "unspecified"))
      (node (ref "USB_C") (pin "A9") (pinfunction "VBUS_A9") (pintype "unspecified"))
      (node (ref "USB_C") (pin "B4") (pinfunction "VBUS_B4") (pintype "unspecified"))
      (node (ref "USB_C") (pin "B9") (pinfunction "VBUS_B9") (pintype "unspecified"))
      (node (ref "V_REG") (pin "3") (pinfunction "VIN_3") (pintype "unspecified"))
    )
    (net (code "68") (name "VCC") (class "Default")
      (node (ref "C4") (pin "2") (pinfunction "2_2") (pintype "input"))
      (node (ref "C6") (pin "2") (pinfunction "2_2") (pintype "input"))
      (node (ref "C7") (pin "2") (pinfunction "2_2") (pintype "input"))
      (node (ref "U10") (pin "23") (pinfunction "VCC(B)_23") (pintype "unspecified"))
      (node (ref "U10") (pin "24") (pinfunction "VCC(B)_24") (pintype "unspecified"))
      (node (ref "U11") (pin "23") (pinfunction "VCC(B)_23") (pintype "unspecified"))
      (node (ref "U11") (pin "24") (pinfunction "VCC(B)_24") (pintype "unspecified"))
      (node (ref "U8") (pin "23") (pinfunction "VCC(B)_23") (pintype "unspecified"))
      (node (ref "U8") (pin "24") (pinfunction "VCC(B)_24") (pintype "unspecified"))
    )
    (net (code "69") (name "VDDA") (class "Default")
      (node (ref "C11") (pin "2") (pinfunction "2_2") (pintype "unspecified"))
      (node (ref "C29") (pin "2") (pinfunction "2_2") (pintype "input"))
      (node (ref "FB1") (pin "2") (pinfunction "2_2") (pintype "unspecified"))
      (node (ref "U7") (pin "13") (pinfunction "VDDA/VREF+_13") (pintype "unspecified"))
    )
    (net (code "70") (name "WE") (class "Default")
      (node (ref "EEPROM1") (pin "27") (pinfunction "WE#_27") (pintype "unspecified"))
      (node (ref "U11") (pin "8") (pinfunction "A6_8") (pintype "unspecified"))
    )
    (net (code "71") (name "WE_STM") (class "Default")
      (node (ref "U11") (pin "16") (pinfunction "B6_16") (pintype "unspecified"))
      (node (ref "U7") (pin "46") (pinfunction "PA13_46") (pintype "unspecified"))
    )
    (net (code "72") (name "unconnected-(CH1G-CTS#-Pad9)") (class "Default")
      (node (ref "CH1G") (pin "9") (pinfunction "CTS#_9") (pintype "unspecified"))
    )
    (net (code "73") (name "unconnected-(CH1G-DCD#-Pad12)") (class "Default")
      (node (ref "CH1G") (pin "12") (pinfunction "DCD#_12") (pintype "unspecified"))
    )
    (net (code "74") (name "unconnected-(CH1G-DSR#-Pad10)") (class "Default")
      (node (ref "CH1G") (pin "10") (pinfunction "DSR#_10") (pintype "unspecified"))
    )
    (net (code "75") (name "unconnected-(CH1G-DTR#-Pad13)") (class "Default")
      (node (ref "CH1G") (pin "13") (pinfunction "DTR#_13") (pintype "unspecified"))
    )
    (net (code "76") (name "unconnected-(CH1G-R232-Pad15)") (class "Default")
      (node (ref "CH1G") (pin "15") (pinfunction "R232_15") (pintype "unspecified"))
    )
    (net (code "77") (name "unconnected-(CH1G-RI#-Pad11)") (class "Default")
      (node (ref "CH1G") (pin "11") (pinfunction "RI#_11") (pintype "unspecified"))
    )
    (net (code "78") (name "unconnected-(CH1G-RTS#-Pad14)") (class "Default")
      (node (ref "CH1G") (pin "14") (pinfunction "RTS#_14") (pintype "unspecified"))
    )
    (net (code "79") (name "unconnected-(EEPROM1-NC-Pad1)") (class "Default")
      (node (ref "EEPROM1") (pin "1") (pinfunction "NC_1") (pintype "unspecified+no_connect"))
    )
    (net (code "80") (name "unconnected-(EEPROM1-NC-Pad26)") (class "Default")
      (node (ref "EEPROM1") (pin "26") (pinfunction "NC_26") (pintype "unspecified+no_connect"))
    )
    (net (code "81") (name "unconnected-(U7-PA15-Pad50)") (class "Default")
      (node (ref "U7") (pin "50") (pinfunction "PA15_50") (pintype "unspecified+no_connect"))
    )
    (net (code "82") (name "unconnected-(U7-PB8-Pad61)") (class "Default")
      (node (ref "U7") (pin "61") (pinfunction "PB8_61") (pintype "unspecified"))
    )
    (net (code "83") (name "unconnected-(U7-PB9-Pad62)") (class "Default")
      (node (ref "U7") (pin "62") (pinfunction "PB9_62") (pintype "unspecified"))
    )
    (net (code "84") (name "unconnected-(U7-PB10-Pad29)") (class "Default")
      (node (ref "U7") (pin "29") (pinfunction "PB10_29") (pintype "unspecified"))
    )
    (net (code "85") (name "unconnected-(U7-PB14-Pad35)") (class "Default")
      (node (ref "U7") (pin "35") (pinfunction "PB14_35") (pintype "unspecified+no_connect"))
    )
    (net (code "86") (name "unconnected-(U7-PB15-Pad36)") (class "Default")
      (node (ref "U7") (pin "36") (pinfunction "PB15_36") (pintype "unspecified+no_connect"))
    )
    (net (code "87") (name "unconnected-(U7-PC0-Pad8)") (class "Default")
      (node (ref "U7") (pin "8") (pinfunction "PC0_8") (pintype "unspecified+no_connect"))
    )
    (net (code "88") (name "unconnected-(U7-PC1-Pad9)") (class "Default")
      (node (ref "U7") (pin "9") (pinfunction "PC1_9") (pintype "unspecified+no_connect"))
    )
    (net (code "89") (name "unconnected-(U7-PC2-Pad10)") (class "Default")
      (node (ref "U7") (pin "10") (pinfunction "PC2_10") (pintype "unspecified+no_connect"))
    )
    (net (code "90") (name "unconnected-(U7-PC3-Pad11)") (class "Default")
      (node (ref "U7") (pin "11") (pinfunction "PC3_11") (pintype "unspecified+no_connect"))
    )
    (net (code "91") (name "unconnected-(U7-PC4-Pad24)") (class "Default")
      (node (ref "U7") (pin "24") (pinfunction "PC4_24") (pintype "unspecified+no_connect"))
    )
    (net (code "92") (name "unconnected-(U7-PC5-Pad25)") (class "Default")
      (node (ref "U7") (pin "25") (pinfunction "PC5_25") (pintype "unspecified+no_connect"))
    )
    (net (code "93") (name "unconnected-(U7-PC8-Pad39)") (class "Default")
      (node (ref "U7") (pin "39") (pinfunction "PC8_39") (pintype "unspecified+no_connect"))
    )
    (net (code "94") (name "unconnected-(U7-PC9-Pad40)") (class "Default")
      (node (ref "U7") (pin "40") (pinfunction "PC9_40") (pintype "unspecified+no_connect"))
    )
    (net (code "95") (name "unconnected-(U7-PC10-Pad51)") (class "Default")
      (node (ref "U7") (pin "51") (pinfunction "PC10_51") (pintype "unspecified+no_connect"))
    )
    (net (code "96") (name "unconnected-(U7-PC11-Pad52)") (class "Default")
      (node (ref "U7") (pin "52") (pinfunction "PC11_52") (pintype "unspecified+no_connect"))
    )
    (net (code "97") (name "unconnected-(U7-PC12-Pad53)") (class "Default")
      (node (ref "U7") (pin "53") (pinfunction "PC12_53") (pintype "unspecified+no_connect"))
    )
    (net (code "98") (name "unconnected-(U7-PC13-Pad2)") (class "Default")
      (node (ref "U7") (pin "2") (pinfunction "PC13_2") (pintype "unspecified+no_connect"))
    )
    (net (code "99") (name "unconnected-(U7-PC14-OSC32_IN-Pad3)") (class "Default")
      (node (ref "U7") (pin "3") (pinfunction "PC14-OSC32_IN_3") (pintype "unspecified+no_connect"))
    )
    (net (code "100") (name "unconnected-(U7-PC15_OSC32_OUT-Pad4)") (class "Default")
      (node (ref "U7") (pin "4") (pinfunction "PC15_OSC32_OUT_4") (pintype "unspecified+no_connect"))
    )
    (net (code "101") (name "unconnected-(U7-PD2-Pad54)") (class "Default")
      (node (ref "U7") (pin "54") (pinfunction "PD2_54") (pintype "unspecified+no_connect"))
    )
    (net (code "102") (name "unconnected-(U11-A8-Pad10)") (class "Default")
      (node (ref "U11") (pin "10") (pinfunction "A8_10") (pintype "unspecified+no_connect"))
    )
    (net (code "103") (name "unconnected-(USB_C-SBU1-PadA8)") (class "Default")
      (node (ref "USB_C") (pin "A8") (pinfunction "SBU1_A8") (pintype "unspecified"))
    )
    (net (code "104") (name "unconnected-(USB_C-SBU2-PadB8)") (class "Default")
      (node (ref "USB_C") (pin "B8") (pinfunction "SBU2_B8") (pintype "unspecified"))
    )
  )
)
